# top.net
KiCad netlist of a schematic drawn in Altium Designer
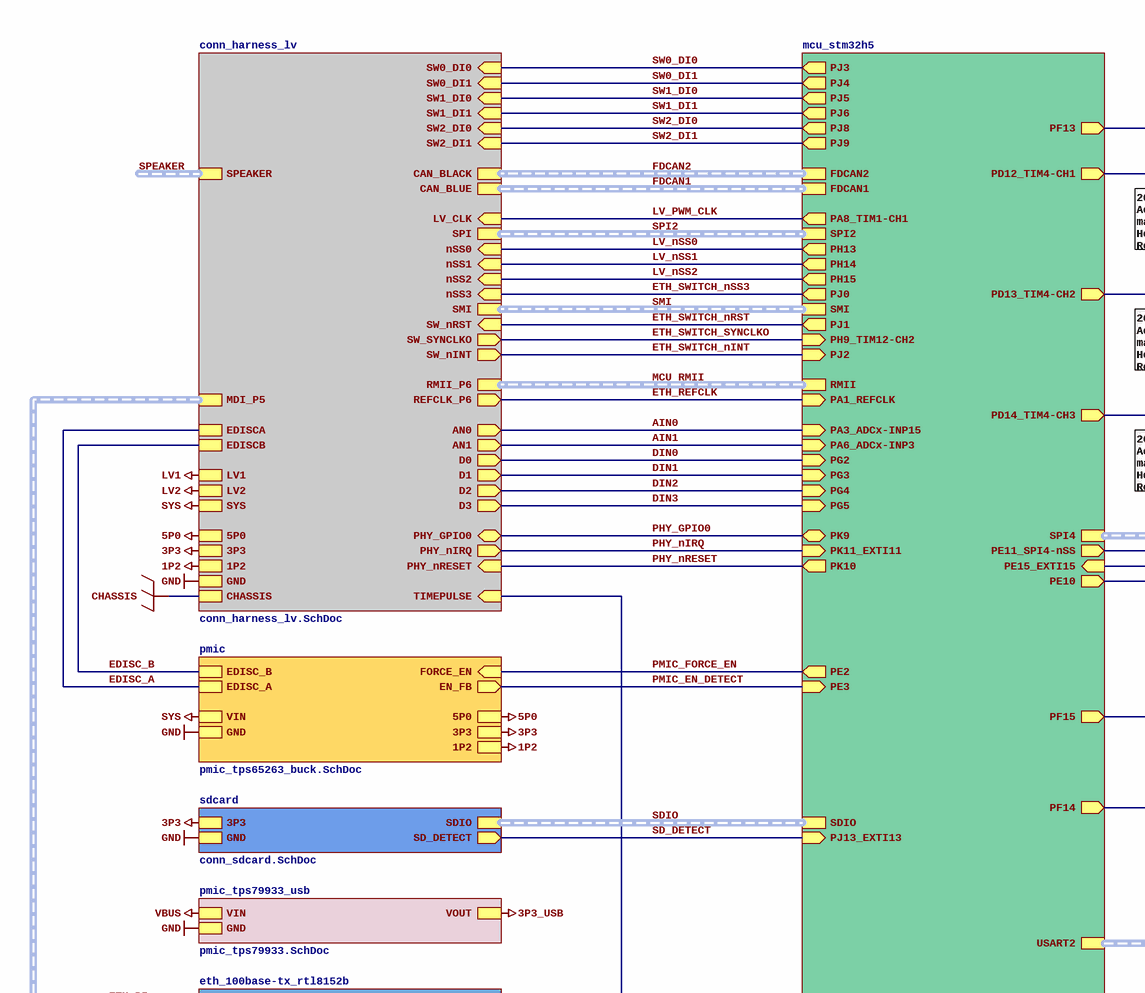
[diagram p0: top.SchDoc, top left]
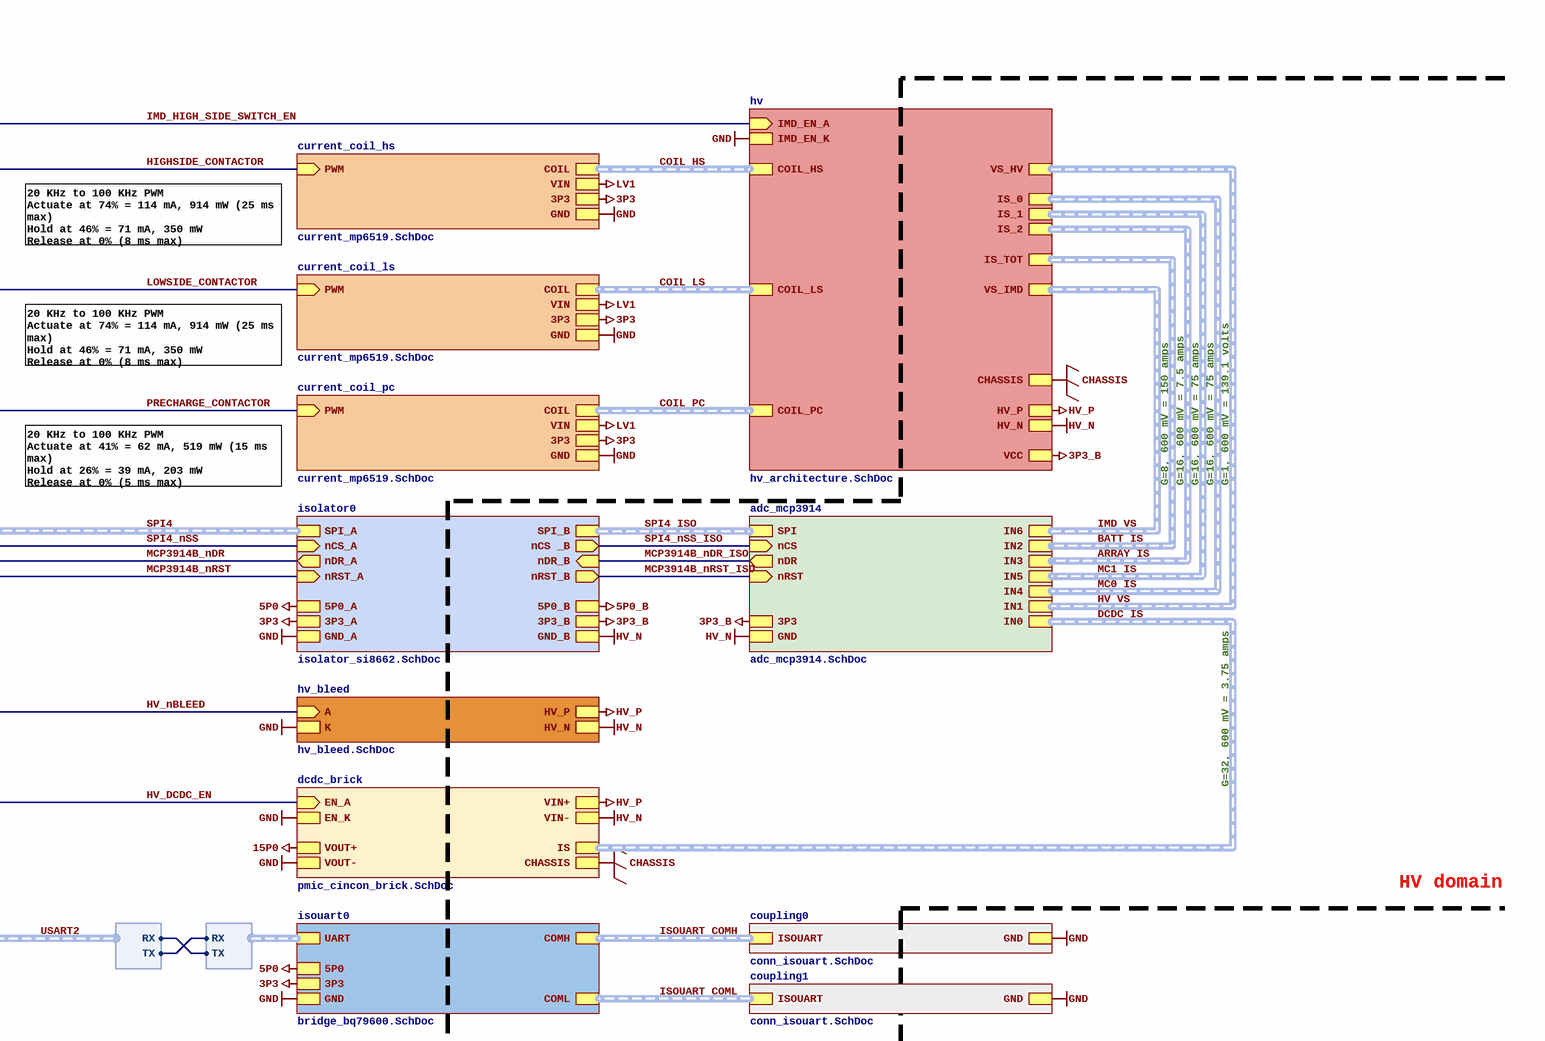
[diagram p1: top.SchDoc, top right]
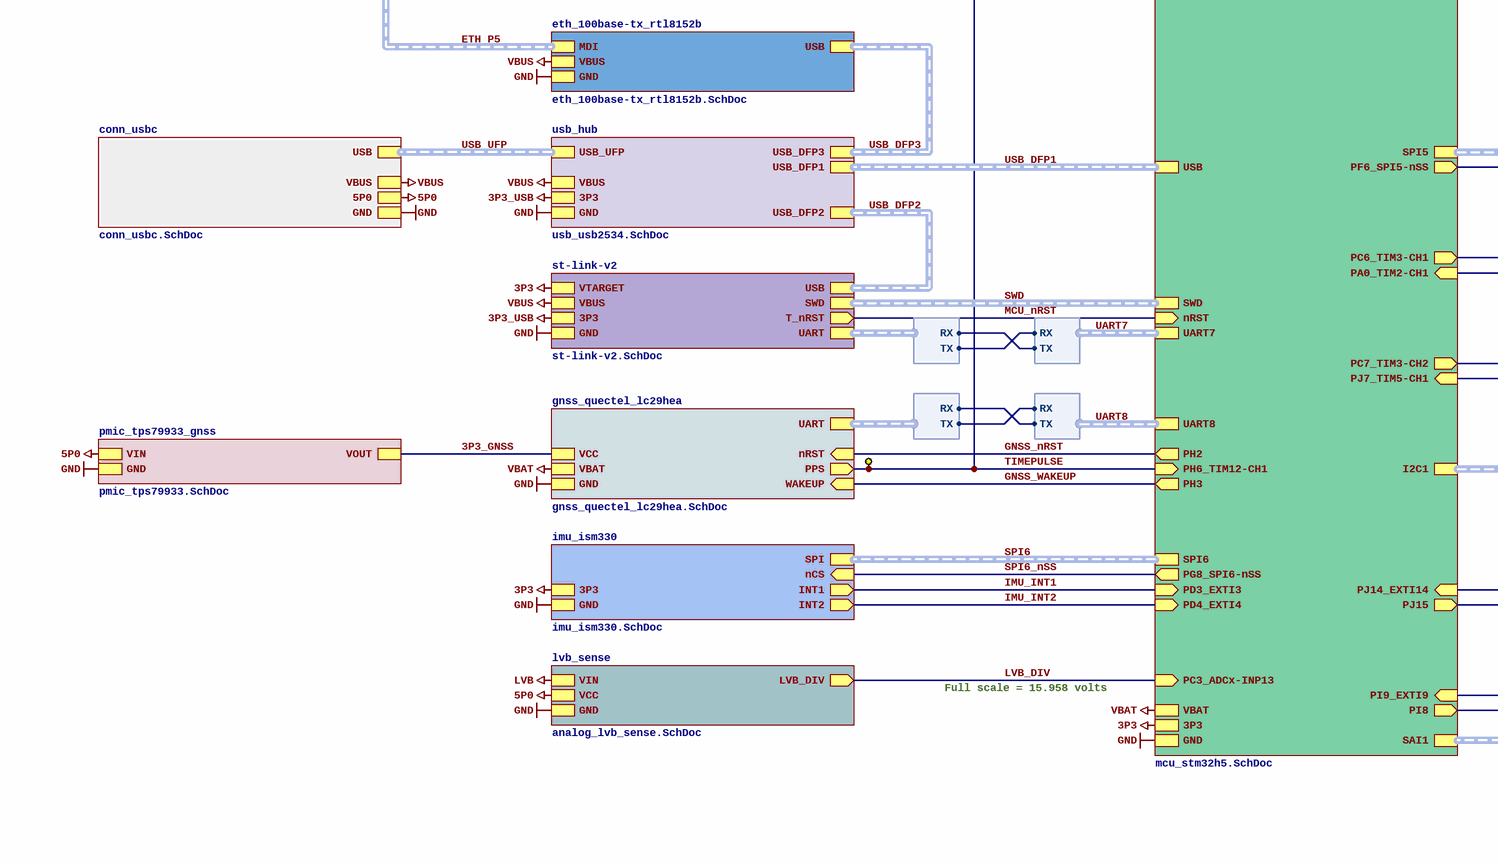
[diagram p2: top.SchDoc, bottom left]
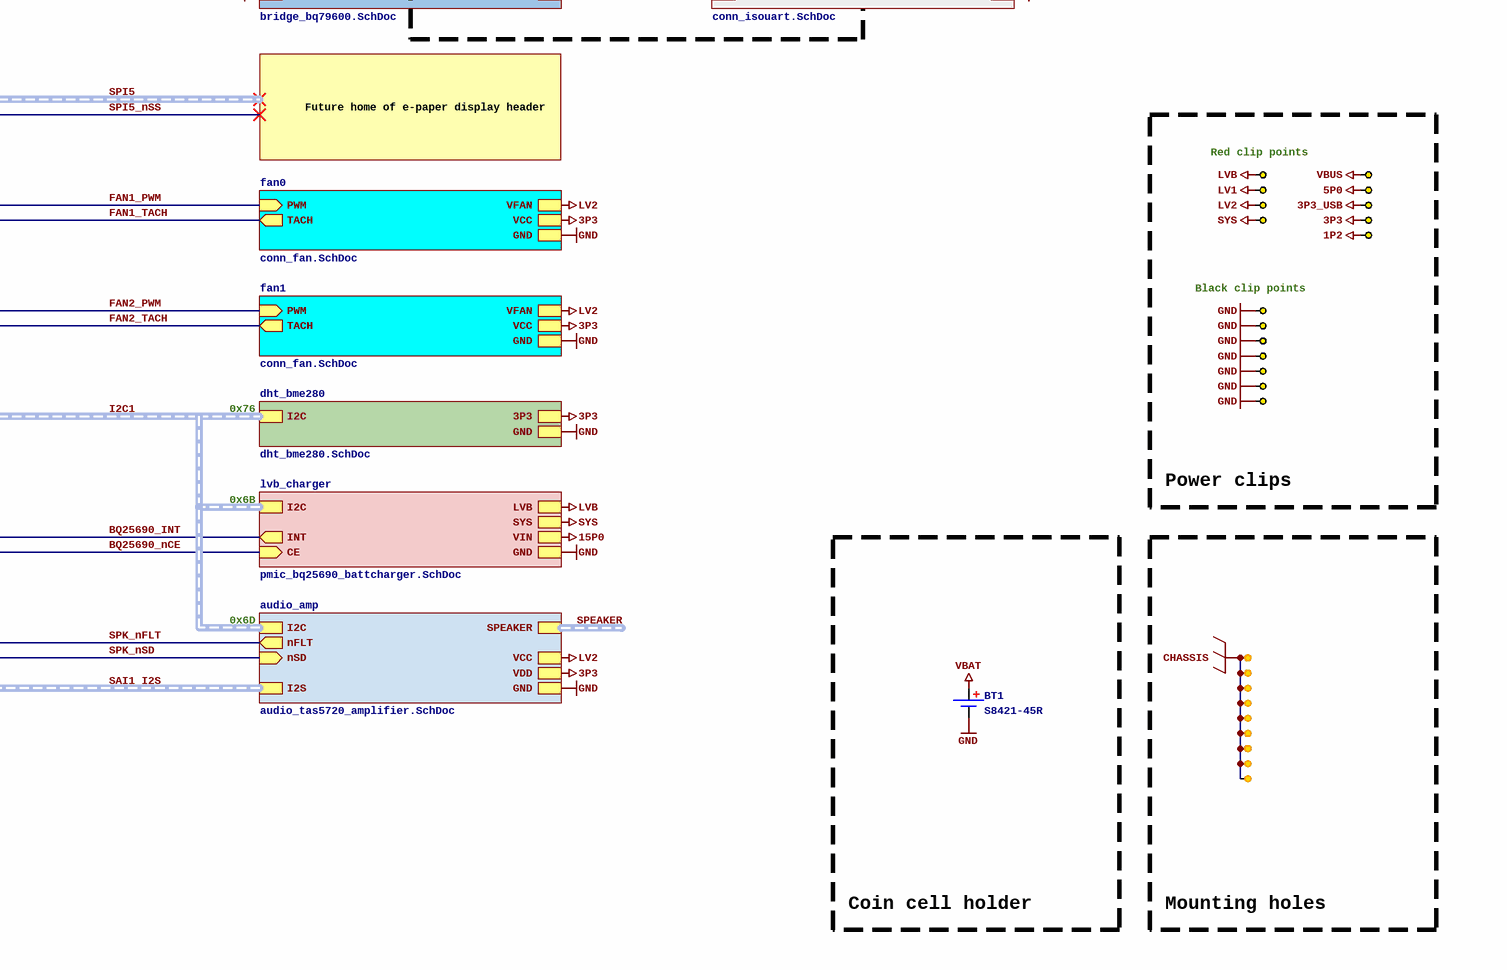
[diagram p3: top.SchDoc, bottom right]

(export (version "E")
  (design (tool "Eeschema 10.0.6"))
  (components
    (comp (ref "BT1")
      (value "S8421-45R")
      (footprint "HOLDER_BATT_CR2032_HARWIN_S8421-45R")
      (description "EZ-Coin Cell Battery Retainer, Horizontal SMT, for CR2032 Coin Cell Batteries")
      (fields (field (name "MANUFACTURER") "Harwin"))
      (libsource (lib "database") (part "S8421-45R"))
    )
    (comp (ref "MH1")
      (value "HOLE")
      (footprint "HOLE_M3")
      (fields (field (name "MANUFACTURER PART NUMBER") "HOLE_M3"))
      (libsource (lib "database") (part "HOLE"))
    )
    (comp (ref "MH2")
      (value "HOLE")
      (footprint "HOLE_M3")
      (fields (field (name "MANUFACTURER PART NUMBER") "HOLE_M3"))
      (libsource (lib "database") (part "HOLE"))
    )
    (comp (ref "MH3")
      (value "HOLE")
      (footprint "HOLE_M3")
      (fields (field (name "MANUFACTURER PART NUMBER") "HOLE_M3"))
      (libsource (lib "database") (part "HOLE"))
    )
    (comp (ref "MH4")
      (value "HOLE")
      (footprint "HOLE_M3")
      (fields (field (name "MANUFACTURER PART NUMBER") "HOLE_M3"))
      (libsource (lib "database") (part "HOLE"))
    )
    (comp (ref "MH5")
      (value "HOLE")
      (footprint "HOLE_M3")
      (fields (field (name "MANUFACTURER PART NUMBER") "HOLE_M3"))
      (libsource (lib "database") (part "HOLE"))
    )
    (comp (ref "MH6")
      (value "HOLE")
      (footprint "HOLE_M3")
      (fields (field (name "MANUFACTURER PART NUMBER") "HOLE_M3"))
      (libsource (lib "database") (part "HOLE"))
    )
    (comp (ref "MH7")
      (value "HOLE")
      (footprint "HOLE_M3")
      (fields (field (name "MANUFACTURER PART NUMBER") "HOLE_M3"))
      (libsource (lib "database") (part "HOLE"))
    )
    (comp (ref "MH8")
      (value "HOLE")
      (footprint "HOLE_M3")
      (fields (field (name "MANUFACTURER PART NUMBER") "HOLE_M3"))
      (libsource (lib "database") (part "HOLE"))
    )
    (comp (ref "MH9")
      (value "HOLE")
      (footprint "HOLE_M3")
      (fields (field (name "MANUFACTURER PART NUMBER") "HOLE_M3"))
      (libsource (lib "database") (part "HOLE"))
    )
    (comp (ref "TP4")
      (value "RH-5002")
      (footprint "TP_RH-5002")
      (description "White through-hole PCB test point")
      (fields (field (name "MANUFACTURER") "ronghe"))
      (libsource (lib "database") (part "__template_testpoint"))
    )
    (comp (ref "TP5")
      (value "RH-5000")
      (footprint "TP_RH-5000")
      (description "Red through-hole PCB test point")
      (fields (field (name "MANUFACTURER") "ronghe"))
      (libsource (lib "database") (part "__template_testpoint"))
    )
    (comp (ref "TP32")
      (value "RH-5000")
      (footprint "TP_RH-5000")
      (description "Red through-hole PCB test point")
      (fields (field (name "MANUFACTURER") "ronghe"))
      (libsource (lib "database") (part "__template_testpoint"))
    )
    (comp (ref "TP33")
      (value "RH-5000")
      (footprint "TP_RH-5000")
      (description "Red through-hole PCB test point")
      (fields (field (name "MANUFACTURER") "ronghe"))
      (libsource (lib "database") (part "__template_testpoint"))
    )
    (comp (ref "TP34")
      (value "RH-5000")
      (footprint "TP_RH-5000")
      (description "Red through-hole PCB test point")
      (fields (field (name "MANUFACTURER") "ronghe"))
      (libsource (lib "database") (part "__template_testpoint"))
    )
    (comp (ref "TP35")
      (value "RH-5000")
      (footprint "TP_RH-5000")
      (description "Red through-hole PCB test point")
      (fields (field (name "MANUFACTURER") "ronghe"))
      (libsource (lib "database") (part "__template_testpoint"))
    )
    (comp (ref "TP36")
      (value "RH-5000")
      (footprint "TP_RH-5000")
      (description "Red through-hole PCB test point")
      (fields (field (name "MANUFACTURER") "ronghe"))
      (libsource (lib "database") (part "__template_testpoint"))
    )
    (comp (ref "TP37")
      (value "RH-5000")
      (footprint "TP_RH-5000")
      (description "Red through-hole PCB test point")
      (fields (field (name "MANUFACTURER") "ronghe"))
      (libsource (lib "database") (part "__template_testpoint"))
    )
    (comp (ref "TP39")
      (value "RH-5001")
      (footprint "TP_RH-5001")
      (description "Black through-hole PCB test point")
      (fields (field (name "MANUFACTURER") "ronghe"))
      (libsource (lib "database") (part "__template_testpoint"))
    )
    (comp (ref "TP41")
      (value "RH-5001")
      (footprint "TP_RH-5001")
      (description "Black through-hole PCB test point")
      (fields (field (name "MANUFACTURER") "ronghe"))
      (libsource (lib "database") (part "__template_testpoint"))
    )
    (comp (ref "TP43")
      (value "RH-5001")
      (footprint "TP_RH-5001")
      (description "Black through-hole PCB test point")
      (fields (field (name "MANUFACTURER") "ronghe"))
      (libsource (lib "database") (part "__template_testpoint"))
    )
    (comp (ref "TP45")
      (value "RH-5001")
      (footprint "TP_RH-5001")
      (description "Black through-hole PCB test point")
      (fields (field (name "MANUFACTURER") "ronghe"))
      (libsource (lib "database") (part "__template_testpoint"))
    )
    (comp (ref "TP46")
      (value "RH-5001")
      (footprint "TP_RH-5001")
      (description "Black through-hole PCB test point")
      (fields (field (name "MANUFACTURER") "ronghe"))
      (libsource (lib "database") (part "__template_testpoint"))
    )
    (comp (ref "TP47")
      (value "RH-5001")
      (footprint "TP_RH-5001")
      (description "Black through-hole PCB test point")
      (fields (field (name "MANUFACTURER") "ronghe"))
      (libsource (lib "database") (part "__template_testpoint"))
    )
    (comp (ref "TP48")
      (value "RH-5001")
      (footprint "TP_RH-5001")
      (description "Black through-hole PCB test point")
      (fields (field (name "MANUFACTURER") "ronghe"))
      (libsource (lib "database") (part "__template_testpoint"))
    )
    (comp (ref "TP89")
      (value "RH-5000")
      (footprint "TP_RH-5000")
      (description "Red through-hole PCB test point")
      (fields (field (name "MANUFACTURER") "ronghe"))
      (libsource (lib "database") (part "__template_testpoint"))
    )
    (comp (ref "TP90")
      (value "RH-5000")
      (footprint "TP_RH-5000")
      (description "Red through-hole PCB test point")
      (fields (field (name "MANUFACTURER") "ronghe"))
      (libsource (lib "database") (part "__template_testpoint"))
    )
  )
  (nets
    (net (code "94") (name "/TIMEPULSE") (class "Default") (node (ref "TP4") (pin "1") (pintype "passive")))
    (net (code "130") (name "1P2") (class "Default") (node (ref "TP37") (pin "1") (pintype "passive")))
    (net (code "131") (name "3P3") (class "Default") (node (ref "TP35") (pin "1") (pintype "passive")))
    (net (code "133") (name "3P3_USB") (class "Default") (node (ref "TP90") (pin "1") (pintype "passive")))
    (net (code "134") (name "5P0") (class "Default") (node (ref "TP33") (pin "1") (pintype "passive")))
    (net (code "137") (name "CHASSIS") (class "Default")
      (node (ref "MH1") (pin "1") (pintype "passive"))
      (node (ref "MH2") (pin "1") (pintype "passive"))
      (node (ref "MH3") (pin "1") (pintype "passive"))
      (node (ref "MH4") (pin "1") (pintype "passive"))
      (node (ref "MH5") (pin "1") (pintype "passive"))
      (node (ref "MH6") (pin "1") (pintype "passive"))
      (node (ref "MH7") (pin "1") (pintype "passive"))
      (node (ref "MH8") (pin "1") (pintype "passive"))
      (node (ref "MH9") (pin "1") (pintype "passive"))
    )
    (net (code "138") (name "GND") (class "Default")
      (node (ref "BT1") (pin "2") (pinfunction "-_2") (pintype "passive"))
      (node (ref "TP39") (pin "1") (pintype "passive"))
      (node (ref "TP41") (pin "1") (pintype "passive"))
      (node (ref "TP43") (pin "1") (pintype "passive"))
      (node (ref "TP45") (pin "1") (pintype "passive"))
      (node (ref "TP46") (pin "1") (pintype "passive"))
      (node (ref "TP47") (pin "1") (pintype "passive"))
      (node (ref "TP48") (pin "1") (pintype "passive"))
    )
    (net (code "141") (name "LV1") (class "Default") (node (ref "TP34") (pin "1") (pintype "passive")))
    (net (code "142") (name "LV2") (class "Default") (node (ref "TP36") (pin "1") (pintype "passive")))
    (net (code "143") (name "LVB") (class "Default") (node (ref "TP32") (pin "1") (pintype "passive")))
    (net (code "144") (name "SYS") (class "Default") (node (ref "TP5") (pin "1") (pintype "passive")))
    (net (code "145") (name "VBAT") (class "Default")
      (node (ref "BT1") (pin "1") (pinfunction "+_1") (pintype "passive"))
    )
    (net (code "146") (name "VBUS") (class "Default") (node (ref "TP89") (pin "1") (pintype "passive")))
  )
)
